# SCH.net
KiCad netlist of a schematic drawn in Altium Designer
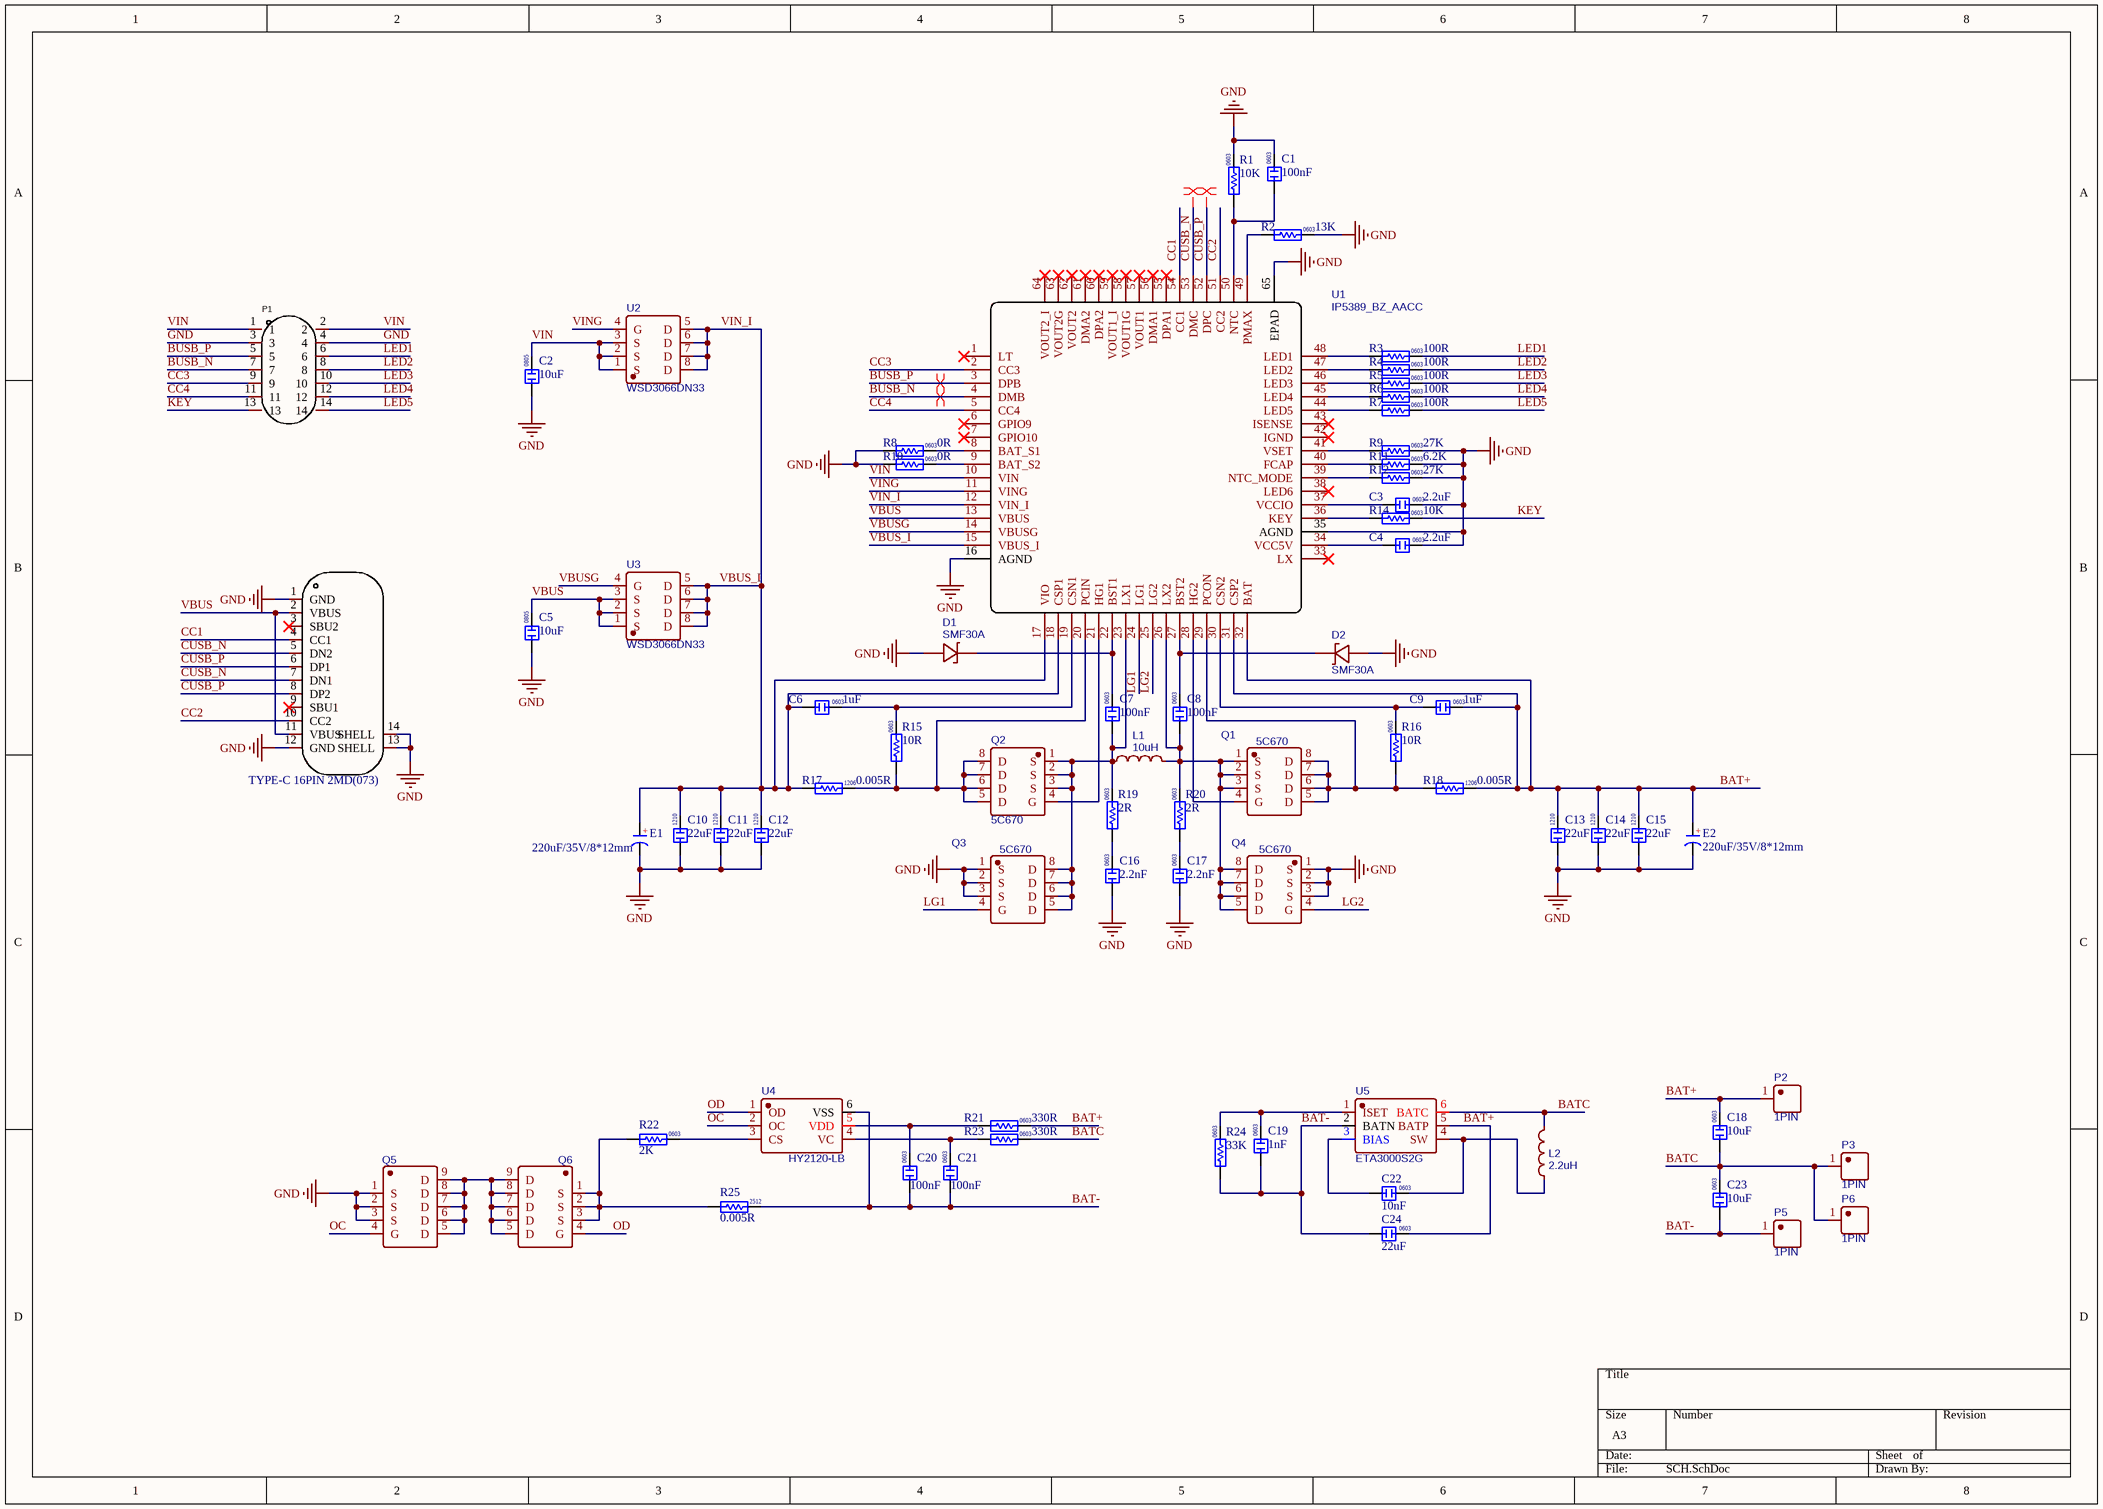
[diagram p0: SCH.SchDoc]

(export (version "E")
  (design (tool "Eeschema 10.0.6"))
  (components
    (comp (ref "C1")
      (value "100nF")
      (footprint "C_0603")
      (description "贴片电容")
      (libsource (lib "VT_SCH_RCL_01") (part "C_0603"))
    )
    (comp (ref "C2")
      (value "10uF")
      (footprint "C_0805")
      (description "贴片电容")
      (libsource (lib "VT_SCH_RCL_01") (part "C_0805"))
    )
    (comp (ref "C3")
      (value "2.2uF")
      (footprint "C_0603")
      (description "贴片电容")
      (libsource (lib "") (part "C_0603_1"))
    )
    (comp (ref "C4")
      (value "2.2uF")
      (footprint "C_0603")
      (description "贴片电容")
      (libsource (lib "") (part "C_0603_1"))
    )
    (comp (ref "C5")
      (value "10uF")
      (footprint "C_0805")
      (description "贴片电容")
      (libsource (lib "VT_SCH_RCL_01") (part "C_0805"))
    )
    (comp (ref "C6")
      (value "1uF")
      (footprint "C_0603")
      (description "贴片电容")
      (libsource (lib "") (part "C_0603_1"))
    )
    (comp (ref "C7")
      (value "100nF")
      (footprint "C_0603")
      (description "贴片电容")
      (libsource (lib "VT_SCH_RCL_01") (part "C_0603"))
    )
    (comp (ref "C8")
      (value "100nF")
      (footprint "C_0603")
      (description "贴片电容")
      (libsource (lib "VT_SCH_RCL_01") (part "C_0603"))
    )
    (comp (ref "C9")
      (value "1uF")
      (footprint "C_0603")
      (description "贴片电容")
      (libsource (lib "") (part "C_0603_1"))
    )
    (comp (ref "C10")
      (value "22uF")
      (footprint "C_1210")
      (description "贴片电容")
      (libsource (lib "VT_SCH_RCL_01") (part "C_1210"))
    )
    (comp (ref "C11")
      (value "22uF")
      (footprint "C_1210")
      (description "贴片电容")
      (libsource (lib "VT_SCH_RCL_01") (part "C_1210"))
    )
    (comp (ref "C12")
      (value "22uF")
      (footprint "C_1210")
      (description "贴片电容")
      (libsource (lib "VT_SCH_RCL_01") (part "C_1210"))
    )
    (comp (ref "C13")
      (value "22uF")
      (footprint "C_1210")
      (description "贴片电容")
      (libsource (lib "VT_SCH_RCL_01") (part "C_1210"))
    )
    (comp (ref "C14")
      (value "22uF")
      (footprint "C_1210")
      (description "贴片电容")
      (libsource (lib "VT_SCH_RCL_01") (part "C_1210"))
    )
    (comp (ref "C15")
      (value "22uF")
      (footprint "C_1210")
      (description "贴片电容")
      (libsource (lib "VT_SCH_RCL_01") (part "C_1210"))
    )
    (comp (ref "C16")
      (value "2.2nF")
      (footprint "C_0603")
      (description "贴片电容")
      (libsource (lib "VT_SCH_RCL_01") (part "C_0603"))
    )
    (comp (ref "C17")
      (value "2.2nF")
      (footprint "C_0603")
      (description "贴片电容")
      (libsource (lib "VT_SCH_RCL_01") (part "C_0603"))
    )
    (comp (ref "C18")
      (value "10uF")
      (footprint "C_0603")
      (description "贴片电容")
      (libsource (lib "VT_SCH_RCL_01") (part "C_0603"))
    )
    (comp (ref "C19")
      (value "1nF")
      (footprint "C_0603")
      (description "贴片电容")
      (libsource (lib "VT_SCH_RCL_01") (part "C_0603"))
    )
    (comp (ref "C20")
      (value "100nF")
      (footprint "C_0603")
      (description "贴片电容")
      (libsource (lib "VT_SCH_RCL_01") (part "C_0603"))
    )
    (comp (ref "C21")
      (value "100nF")
      (footprint "C_0603")
      (description "贴片电容")
      (libsource (lib "VT_SCH_RCL_01") (part "C_0603"))
    )
    (comp (ref "C22")
      (value "10nF")
      (footprint "C_0603")
      (description "贴片电容")
      (libsource (lib "") (part "C_0603_1"))
    )
    (comp (ref "C23")
      (value "10uF")
      (footprint "C_0603")
      (description "贴片电容")
      (libsource (lib "VT_SCH_RCL_01") (part "C_0603"))
    )
    (comp (ref "C24")
      (value "22uF")
      (footprint "C_0603")
      (description "贴片电容")
      (libsource (lib "") (part "C_0603_1"))
    )
    (comp (ref "D1")
      (value "SMF30A")
      (footprint "SOD-123FL_L2.6-W1.6-LS3.4-R-FD")
      (fields (field (name "MANUFACTURER") "(MDD) Jiangsu Yutai Elec") (field (name "CONTRIBUTOR") "LCSC"))
      (libsource (lib "altium-import") (part "root_2_SMF30A_C364281_"))
    )
    (comp (ref "D2")
      (value "SMF30A")
      (footprint "SOD-123FL_L2.6-W1.6-LS3.4-R-FD")
      (fields (field (name "MANUFACTURER") "(MDD) Jiangsu Yutai Elec") (field (name "CONTRIBUTOR") "LCSC"))
      (libsource (lib "altium-import") (part "root_0_SMF30A_C364281_"))
    )
    (comp (ref "E1")
      (value "220uF/35V/8*12mm")
      (footprint "CAP 3.5*8*12_L")
      (description "直插固态电容")
      (fields (field (name "版权归属") "源创客"))
      (libsource (lib "电阻-电容-电感") (part "C-CS"))
    )
    (comp (ref "E2")
      (value "220uF/35V/8*12mm")
      (footprint "CAP 3.5*8*12_L")
      (description "直插固态电容")
      (fields (field (name "版权归属") "源创客"))
      (libsource (lib "电阻-电容-电感") (part "C-CS"))
    )
    (comp (ref "L1")
      (value "10uH")
      (footprint "IND-SMD_L11.0-W10.2")
      (description "PSPMAA1040H-100M-ANP")
      (fields
        (field (name "MANUFACTURER") "Sunlord")
        (field (name "MANUFACTURER PART") "MWSA1206S-5R6MT")
        (field (name "CONTRIBUTOR") "LCSC")
      )
      (libsource (lib "altium-import") (part "root_0_5.6uH_"))
    )
    (comp (ref "L2")
      (value "2.2uH")
      (footprint "L_4*4")
      (fields
        (field (name "MANUFACTURER") "EMTEK")
        (field (name "MANUFACTURER PART") "PHC0420-2R2M-T")
        (field (name "CONTRIBUTOR") "LCSC")
      )
      (libsource (lib "altium-import") (part "root_1_2.2uH_"))
    )
    (comp (ref "P1")
      (value "X1321WR-2x07J-C40D18")
      (footprint "HDR-TH_14P-P1.27-H-M-R2-C7-S1.27-W7.5-N2")
      (description "插针")
      (fields (field (name "MANUFACTURER") "XKB Connectivity(中国星坤)"))
      (libsource (lib "altium-import") (part "root_0_X1321WR-2x07J-C40D18_"))
    )
    (comp (ref "P2")
      (value "1PIN")
      (footprint "1PIN")
      (description "焊点")
      (fields
        (field (name "MANUFACTURER") "ZHENGLING")
        (field (name "MANUFACTURER PART") "Z-211-0311-0021-001")
        (field (name "CONTRIBUTOR") "LCSC")
      )
      (libsource (lib "DHO800_Battery_Pack_IP5389_V1.0_2") (part "1PIN"))
    )
    (comp (ref "P3")
      (value "1PIN")
      (footprint "1PIN")
      (description "焊点")
      (fields
        (field (name "MANUFACTURER") "ZHENGLING")
        (field (name "MANUFACTURER PART") "Z-211-0311-0021-001")
        (field (name "CONTRIBUTOR") "LCSC")
      )
      (libsource (lib "DHO800_Battery_Pack_IP5389_V1.0_2") (part "1PIN"))
    )
    (comp (ref "P5")
      (value "1PIN")
      (footprint "1PIN")
      (description "焊点")
      (fields
        (field (name "MANUFACTURER") "ZHENGLING")
        (field (name "MANUFACTURER PART") "Z-211-0311-0021-001")
        (field (name "CONTRIBUTOR") "LCSC")
      )
      (libsource (lib "DHO800_Battery_Pack_IP5389_V1.0_2") (part "1PIN"))
    )
    (comp (ref "P6")
      (value "1PIN")
      (footprint "1PIN")
      (description "焊点")
      (fields
        (field (name "MANUFACTURER") "ZHENGLING")
        (field (name "MANUFACTURER PART") "Z-211-0311-0021-001")
        (field (name "CONTRIBUTOR") "LCSC")
      )
      (libsource (lib "DHO800_Battery_Pack_IP5389_V1.0_2") (part "1PIN"))
    )
    (comp (ref "Q1")
      (value "5C670")
      (footprint "DFN-5_L6.1-W5.1-P1.27-BL")
      (description "NTMFS5C670NLT1G")
      (fields (field (name "MANUFACTURER") "ON Semicon") (field (name "CONTRIBUTOR") "LCSC"))
      (libsource (lib "") (part "root_0_5C670__1"))
    )
    (comp (ref "Q2")
      (value "5C670")
      (footprint "DFN-5_L6.1-W5.1-P1.27-BL")
      (description "NTMFS5C670NLT1G")
      (fields (field (name "MANUFACTURER") "ON Semicon") (field (name "CONTRIBUTOR") "LCSC"))
      (libsource (lib "altium-import") (part "root_0_5C670_"))
    )
    (comp (ref "Q3")
      (value "5C670")
      (footprint "DFN-5_L6.1-W5.1-P1.27-BL")
      (description "NTMFS5C670NLT1G")
      (fields (field (name "MANUFACTURER") "ON Semicon") (field (name "CONTRIBUTOR") "LCSC"))
      (libsource (lib "") (part "root_0_5C670__1"))
    )
    (comp (ref "Q4")
      (value "5C670")
      (footprint "DFN-5_L6.1-W5.1-P1.27-BL")
      (description "NTMFS5C670NLT1G")
      (fields (field (name "MANUFACTURER") "ON Semicon") (field (name "CONTRIBUTOR") "LCSC"))
      (libsource (lib "altium-import") (part "root_0_5C670_"))
    )
    (comp (ref "Q5")
      (value "TPH1R403NL")
      (footprint "DSOP-8_L5.0-W5.0-P1.27-LS6.0-BL-EP")
      (fields
        (field (name "MANUFACTURER") "Vishay Intertech")
        (field (name "MANUFACTURER PART") "SIRA12DP-T1-GE3")
        (field (name "CONTRIBUTOR") "LCSC")
      )
      (libsource (lib "") (part "root_0_SIRA12DP-T1-GE3__1"))
    )
    (comp (ref "Q6")
      (value "TPH1R403NL")
      (footprint "DSOP-8_L5.0-W5.0-P1.27-LS6.0-BL-EP")
      (fields
        (field (name "MANUFACTURER") "Vishay Intertech")
        (field (name "MANUFACTURER PART") "SIRA12DP-T1-GE3")
        (field (name "CONTRIBUTOR") "LCSC")
      )
      (libsource (lib "altium-import") (part "root_0_SIRA12DP-T1-GE3_"))
    )
    (comp (ref "R1")
      (value "10K")
      (footprint "R_0603")
      (description "贴片电阻")
      (libsource (lib "") (part "R_0603_1"))
    )
    (comp (ref "R2")
      (value "13K")
      (footprint "R_0603")
      (description "贴片电阻")
      (libsource (lib "VT_SCH_RCL_01") (part "R_0603"))
    )
    (comp (ref "R3")
      (value "100R")
      (footprint "R_0603")
      (description "贴片电阻")
      (libsource (lib "VT_SCH_RCL_01") (part "R_0603"))
    )
    (comp (ref "R4")
      (value "100R")
      (footprint "R_0603")
      (description "贴片电阻")
      (libsource (lib "VT_SCH_RCL_01") (part "R_0603"))
    )
    (comp (ref "R5")
      (value "100R")
      (footprint "R_0603")
      (description "贴片电阻")
      (libsource (lib "VT_SCH_RCL_01") (part "R_0603"))
    )
    (comp (ref "R6")
      (value "100R")
      (footprint "R_0603")
      (description "贴片电阻")
      (libsource (lib "VT_SCH_RCL_01") (part "R_0603"))
    )
    (comp (ref "R7")
      (value "100R")
      (footprint "R_0603")
      (description "贴片电阻")
      (libsource (lib "VT_SCH_RCL_01") (part "R_0603"))
    )
    (comp (ref "R8")
      (value "0R")
      (footprint "R_0603")
      (description "贴片电阻")
      (libsource (lib "VT_SCH_RCL_01") (part "R_0603"))
    )
    (comp (ref "R9")
      (value "27K")
      (footprint "R_0603")
      (description "贴片电阻")
      (libsource (lib "VT_SCH_RCL_01") (part "R_0603"))
    )
    (comp (ref "R10")
      (value "0R")
      (footprint "R_0603")
      (description "贴片电阻")
      (libsource (lib "VT_SCH_RCL_01") (part "R_0603"))
    )
    (comp (ref "R11")
      (value "6.2K")
      (footprint "R_0603")
      (description "贴片电阻")
      (libsource (lib "VT_SCH_RCL_01") (part "R_0603"))
    )
    (comp (ref "R12")
      (value "27K")
      (footprint "R_0603")
      (description "贴片电阻")
      (libsource (lib "VT_SCH_RCL_01") (part "R_0603"))
    )
    (comp (ref "R14")
      (value "10K")
      (footprint "R_0603")
      (description "贴片电阻")
      (libsource (lib "VT_SCH_RCL_01") (part "R_0603"))
    )
    (comp (ref "R15")
      (value "10R")
      (footprint "R_0603")
      (description "贴片电阻")
      (libsource (lib "") (part "R_0603_1"))
    )
    (comp (ref "R16")
      (value "10R")
      (footprint "R_0603")
      (description "贴片电阻")
      (libsource (lib "") (part "R_0603_1"))
    )
    (comp (ref "R17")
      (value "0.005R")
      (footprint "R_1206")
      (description "贴片电阻")
      (libsource (lib "VT_SCH_RCL_01") (part "R_1206"))
    )
    (comp (ref "R18")
      (value "0.005R")
      (footprint "R_1206")
      (description "贴片电阻")
      (libsource (lib "VT_SCH_RCL_01") (part "R_1206"))
    )
    (comp (ref "R19")
      (value "2R")
      (footprint "R_0603")
      (description "贴片电阻")
      (libsource (lib "") (part "R_0603_1"))
    )
    (comp (ref "R20")
      (value "2R")
      (footprint "R_0603")
      (description "贴片电阻")
      (libsource (lib "") (part "R_0603_1"))
    )
    (comp (ref "R21")
      (value "330R")
      (footprint "R_0603")
      (description "贴片电阻")
      (libsource (lib "VT_SCH_RCL_01") (part "R_0603"))
    )
    (comp (ref "R22")
      (value "2K")
      (footprint "R_0603")
      (description "贴片电阻")
      (libsource (lib "VT_SCH_RCL_01") (part "R_0603"))
    )
    (comp (ref "R23")
      (value "330R")
      (footprint "R_0603")
      (description "贴片电阻")
      (libsource (lib "VT_SCH_RCL_01") (part "R_0603"))
    )
    (comp (ref "R24")
      (value "33K")
      (footprint "R_0603")
      (description "贴片电阻")
      (libsource (lib "") (part "R_0603_1"))
    )
    (comp (ref "R25")
      (value "0.005R")
      (footprint "R_2512")
      (description "贴片电阻")
      (libsource (lib "VT_SCH_RCL_01") (part "R_2512"))
    )
    (comp (ref "U1")
      (value "IP5389_BZ_AACC")
      (footprint "QFN-64_IP5389")
      (description "芯片")
      (fields (field (name "CONTRIBUTOR") "LoveLoli"))
      (libsource (lib "DHO800_Battery_Pack_IP5389_V1.0_2") (part "IP5389_BZ_AACC"))
    )
    (comp (ref "U2")
      (value "WSD3066DN33")
      (footprint "DFN-8_L3.3-W3.3-P0.65-BL")
      (description "NMOS管")
      (fields
        (field (name "MANUFACTURER PART") "NTMFS5C670NLT1G")
        (field (name "MANUFACTURER") "ON Semicon")
        (field (name "CONTRIBUTOR") "LCSC")
      )
      (libsource (lib "DHO800_Battery_Pack_IP5389_V1.0_2") (part "WSD3066DN33"))
    )
    (comp (ref "U3")
      (value "WSD3066DN33")
      (footprint "DFN-8_L3.3-W3.3-P0.65-BL")
      (description "NMOS管")
      (fields
        (field (name "MANUFACTURER PART") "NTMFS5C670NLT1G")
        (field (name "MANUFACTURER") "ON Semicon")
        (field (name "CONTRIBUTOR") "LCSC")
      )
      (libsource (lib "DHO800_Battery_Pack_IP5389_V1.0_2") (part "WSD3066DN33"))
    )
    (comp (ref "U4")
      (value "HY2120-LB")
      (footprint "SOT-23-6_L2.9-W1.6-P0.95-LS2.8-BR")
      (fields (field (name "MANUFACTURER") "HYCON") (field (name "CONTRIBUTOR") "LCSC"))
      (libsource (lib "altium-import") (part "root_0_HY2120-LB_"))
    )
    (comp (ref "U5")
      (value "ETA3000S2G")
      (footprint "SOT-23-6_L2.9-W1.6-P0.95-LS2.8-BL")
      (description "芯片")
      (fields (field (name "MANUFACTURER") "ETA(钰泰)") (field (name "CONTRIBUTOR") "ryq1212"))
      (libsource (lib "altium-import") (part "root_0_ETA3000S2G_"))
    )
    (comp (ref "USB1")
      (value "TYPE-C 16PIN 2MD(073)")
      (footprint "USB-C-SMD_TYPE-C-6PIN-2MD-073")
      (description "USB C母座")
      (fields (field (name "MANUFACTURER") "SHOU HAN(首韩)"))
      (libsource (lib "DHO800_Battery_Pack_IP5389_V1.0") (part "TYPE-C 16PIN 2MD(073)"))
    )
  )
  (nets
    (net (code "1") (name "/BAT+") (class "Default")
      (node (ref "C13") (pin "2") (pinfunction "2_2") (pintype "passive"))
      (node (ref "C14") (pin "2") (pinfunction "2_2") (pintype "passive"))
      (node (ref "C15") (pin "2") (pinfunction "2_2") (pintype "passive"))
      (node (ref "C18") (pin "2") (pinfunction "2_2") (pintype "passive"))
      (node (ref "C24") (pin "2") (pinfunction "2_2") (pintype "passive"))
      (node (ref "C9") (pin "2") (pinfunction "2_2") (pintype "passive"))
      (node (ref "E2") (pin "1") (pinfunction "A_1") (pintype "passive"))
      (node (ref "P2") (pin "1") (pintype "passive"))
      (node (ref "R18") (pin "2") (pinfunction "2_2") (pintype "passive"))
      (node (ref "R21") (pin "2") (pinfunction "2_2") (pintype "passive"))
      (node (ref "U1") (pin "31") (pinfunction "CSP2_31") (pintype "passive"))
      (node (ref "U1") (pin "32") (pinfunction "BAT_32") (pintype "passive"))
      (node (ref "U5") (pin "5") (pinfunction "BATP_5") (pintype "passive"))
    )
    (net (code "2") (name "/BAT-") (class "Default")
      (node (ref "C19") (pin "1") (pinfunction "1_1") (pintype "passive"))
      (node (ref "C20") (pin "1") (pinfunction "1_1") (pintype "passive"))
      (node (ref "C21") (pin "1") (pinfunction "1_1") (pintype "passive"))
      (node (ref "C23") (pin "1") (pinfunction "1_1") (pintype "passive"))
      (node (ref "C24") (pin "1") (pinfunction "1_1") (pintype "passive"))
      (node (ref "P5") (pin "1") (pintype "passive"))
      (node (ref "R24") (pin "1") (pinfunction "1_1") (pintype "passive"))
      (node (ref "R25") (pin "2") (pinfunction "2_2") (pintype "passive"))
      (node (ref "U4") (pin "6") (pinfunction "VSS_6") (pintype "passive"))
      (node (ref "U5") (pin "2") (pinfunction "BATN_2") (pintype "passive"))
    )
    (net (code "3") (name "/BATC") (class "Default")
      (node (ref "C18") (pin "1") (pinfunction "1_1") (pintype "passive"))
      (node (ref "C23") (pin "2") (pinfunction "2_2") (pintype "passive"))
      (node (ref "L2") (pin "2") (pinfunction "2_2") (pintype "passive"))
      (node (ref "P3") (pin "1") (pintype "passive"))
      (node (ref "P6") (pin "1") (pintype "passive"))
      (node (ref "R23") (pin "2") (pinfunction "2_2") (pintype "passive"))
      (node (ref "U5") (pin "6") (pinfunction "BATC_6") (pintype "passive"))
    )
    (net (code "4") (name "/BUSB_N") (class "Default")
      (node (ref "P1") (pin "7") (pinfunction "7_7") (pintype "passive"))
      (node (ref "U1") (pin "4") (pinfunction "DMB_4") (pintype "passive"))
    )
    (net (code "5") (name "/BUSB_P") (class "Default")
      (node (ref "P1") (pin "5") (pinfunction "5_5") (pintype "passive"))
      (node (ref "U1") (pin "3") (pinfunction "DPB_3") (pintype "passive"))
    )
    (net (code "6") (name "/CC1") (class "Default")
      (node (ref "U1") (pin "54") (pinfunction "CC1_54") (pintype "passive"))
      (node (ref "USB1") (pin "4") (pinfunction "CC1_4") (pintype "passive"))
    )
    (net (code "7") (name "/CC2") (class "Default")
      (node (ref "U1") (pin "51") (pinfunction "CC2_51") (pintype "passive"))
      (node (ref "USB1") (pin "10") (pinfunction "CC2_10") (pintype "passive"))
    )
    (net (code "8") (name "/CC3") (class "Default")
      (node (ref "P1") (pin "9") (pinfunction "9_9") (pintype "passive"))
      (node (ref "U1") (pin "2") (pinfunction "CC3_2") (pintype "passive"))
    )
    (net (code "9") (name "/CC4") (class "Default")
      (node (ref "P1") (pin "11") (pinfunction "11_11") (pintype "passive"))
      (node (ref "U1") (pin "5") (pinfunction "CC4_5") (pintype "passive"))
    )
    (net (code "10") (name "/CUSB_N") (class "Default")
      (node (ref "U1") (pin "53") (pinfunction "DMC_53") (pintype "passive"))
      (node (ref "USB1") (pin "5") (pinfunction "DN2_5") (pintype "passive"))
      (node (ref "USB1") (pin "7") (pinfunction "DN1_7") (pintype "passive"))
    )
    (net (code "11") (name "/CUSB_P") (class "Default")
      (node (ref "U1") (pin "52") (pinfunction "DPC_52") (pintype "passive"))
      (node (ref "USB1") (pin "6") (pinfunction "DP1_6") (pintype "passive"))
      (node (ref "USB1") (pin "8") (pinfunction "DP2_8") (pintype "passive"))
    )
    (net (code "12") (name "/KEY") (class "Default")
      (node (ref "P1") (pin "13") (pinfunction "13_13") (pintype "passive"))
      (node (ref "R14") (pin "2") (pinfunction "2_2") (pintype "passive"))
    )
    (net (code "13") (name "/LED1") (class "Default")
      (node (ref "P1") (pin "6") (pinfunction "6_6") (pintype "passive"))
      (node (ref "R3") (pin "2") (pinfunction "2_2") (pintype "passive"))
    )
    (net (code "14") (name "/LED2") (class "Default")
      (node (ref "P1") (pin "8") (pinfunction "8_8") (pintype "passive"))
      (node (ref "R4") (pin "2") (pinfunction "2_2") (pintype "passive"))
    )
    (net (code "15") (name "/LED3") (class "Default")
      (node (ref "P1") (pin "10") (pinfunction "10_10") (pintype "passive"))
      (node (ref "R5") (pin "2") (pinfunction "2_2") (pintype "passive"))
    )
    (net (code "16") (name "/LED4") (class "Default")
      (node (ref "P1") (pin "12") (pinfunction "12_12") (pintype "passive"))
      (node (ref "R6") (pin "2") (pinfunction "2_2") (pintype "passive"))
    )
    (net (code "17") (name "/LED5") (class "Default")
      (node (ref "P1") (pin "14") (pinfunction "14_14") (pintype "passive"))
      (node (ref "R7") (pin "2") (pinfunction "2_2") (pintype "passive"))
    )
    (net (code "18") (name "/LG1") (class "Default")
      (node (ref "Q3") (pin "4") (pinfunction "G_4") (pintype "passive"))
      (node (ref "U1") (pin "24") (pinfunction "LG1_24") (pintype "passive"))
    )
    (net (code "19") (name "/LG2") (class "Default")
      (node (ref "Q4") (pin "4") (pinfunction "G_4") (pintype "passive"))
      (node (ref "U1") (pin "25") (pinfunction "LG2_25") (pintype "passive"))
    )
    (net (code "20") (name "/OC") (class "Default")
      (node (ref "Q5") (pin "4") (pinfunction "G_4") (pintype "passive"))
      (node (ref "U4") (pin "2") (pinfunction "OC_2") (pintype "passive"))
    )
    (net (code "21") (name "/OD") (class "Default")
      (node (ref "Q6") (pin "4") (pinfunction "G_4") (pintype "passive"))
      (node (ref "U4") (pin "1") (pinfunction "OD_1") (pintype "passive"))
    )
    (net (code "22") (name "/VBUS") (class "Default")
      (node (ref "C5") (pin "2") (pinfunction "2_2") (pintype "passive"))
      (node (ref "U1") (pin "13") (pinfunction "VBUS_13") (pintype "passive"))
      (node (ref "U3") (pin "1") (pinfunction "S_1") (pintype "passive"))
      (node (ref "U3") (pin "2") (pinfunction "S_2") (pintype "passive"))
      (node (ref "U3") (pin "3") (pinfunction "S_3") (pintype "passive"))
      (node (ref "USB1") (pin "11") (pinfunction "VBUS_11") (pintype "passive"))
      (node (ref "USB1") (pin "2") (pinfunction "VBUS_2") (pintype "passive"))
    )
    (net (code "23") (name "/VBUSG") (class "Default")
      (node (ref "U1") (pin "14") (pinfunction "VBUSG_14") (pintype "passive"))
      (node (ref "U3") (pin "4") (pinfunction "G_4") (pintype "passive"))
    )
    (net (code "24") (name "/VBUS_I") (class "Default")
      (node (ref "C10") (pin "2") (pinfunction "2_2") (pintype "passive"))
      (node (ref "C11") (pin "2") (pinfunction "2_2") (pintype "passive"))
      (node (ref "C12") (pin "2") (pinfunction "2_2") (pintype "passive"))
      (node (ref "C6") (pin "1") (pinfunction "1_1") (pintype "passive"))
      (node (ref "E1") (pin "1") (pinfunction "A_1") (pintype "passive"))
      (node (ref "R17") (pin "1") (pinfunction "1_1") (pintype "passive"))
      (node (ref "U1") (pin "12") (pinfunction "VIN_I_12") (pintype "passive"))
      (node (ref "U1") (pin "15") (pinfunction "VBUS_I_15") (pintype "passive"))
      (node (ref "U1") (pin "17") (pinfunction "VIO_17") (pintype "passive"))
      (node (ref "U1") (pin "18") (pinfunction "CSP1_18") (pintype "passive"))
      (node (ref "U2") (pin "5") (pinfunction "D_5") (pintype "passive"))
      (node (ref "U2") (pin "6") (pinfunction "D_6") (pintype "passive"))
      (node (ref "U2") (pin "7") (pinfunction "D_7") (pintype "passive"))
      (node (ref "U2") (pin "8") (pinfunction "D_8") (pintype "passive"))
      (node (ref "U3") (pin "5") (pinfunction "D_5") (pintype "passive"))
      (node (ref "U3") (pin "6") (pinfunction "D_6") (pintype "passive"))
      (node (ref "U3") (pin "7") (pinfunction "D_7") (pintype "passive"))
      (node (ref "U3") (pin "8") (pinfunction "D_8") (pintype "passive"))
    )
    (net (code "25") (name "/VIN") (class "Default")
      (node (ref "C2") (pin "2") (pinfunction "2_2") (pintype "passive"))
      (node (ref "P1") (pin "1") (pinfunction "1_1") (pintype "passive"))
      (node (ref "P1") (pin "2") (pinfunction "2_2") (pintype "passive"))
      (node (ref "U1") (pin "10") (pinfunction "VIN_10") (pintype "passive"))
      (node (ref "U2") (pin "1") (pinfunction "S_1") (pintype "passive"))
      (node (ref "U2") (pin "2") (pinfunction "S_2") (pintype "passive"))
      (node (ref "U2") (pin "3") (pinfunction "S_3") (pintype "passive"))
    )
    (net (code "26") (name "/VING") (class "Default")
      (node (ref "U1") (pin "11") (pinfunction "VING_11") (pintype "passive"))
      (node (ref "U2") (pin "4") (pinfunction "G_4") (pintype "passive"))
    )
    (net (code "27") (name "GND") (class "Default")
      (node (ref "C1") (pin "2") (pinfunction "2_2") (pintype "passive"))
      (node (ref "C10") (pin "1") (pinfunction "1_1") (pintype "passive"))
      (node (ref "C11") (pin "1") (pinfunction "1_1") (pintype "passive"))
      (node (ref "C12") (pin "1") (pinfunction "1_1") (pintype "passive"))
      (node (ref "C13") (pin "1") (pinfunction "1_1") (pintype "passive"))
      (node (ref "C14") (pin "1") (pinfunction "1_1") (pintype "passive"))
      (node (ref "C15") (pin "1") (pinfunction "1_1") (pintype "passive"))
      (node (ref "C16") (pin "1") (pinfunction "1_1") (pintype "passive"))
      (node (ref "C17") (pin "1") (pinfunction "1_1") (pintype "passive"))
      (node (ref "C2") (pin "1") (pinfunction "1_1") (pintype "passive"))
      (node (ref "C3") (pin "2") (pinfunction "2_2") (pintype "passive"))
      (node (ref "C4") (pin "2") (pinfunction "2_2") (pintype "passive"))
      (node (ref "C5") (pin "1") (pinfunction "1_1") (pintype "passive"))
      (node (ref "D1") (pin "2") (pinfunction "A_2") (pintype "passive"))
      (node (ref "D2") (pin "2") (pinfunction "A_2") (pintype "passive"))
      (node (ref "E1") (pin "2") (pinfunction "K_2") (pintype "passive"))
      (node (ref "E2") (pin "2") (pinfunction "K_2") (pintype "passive"))
      (node (ref "P1") (pin "3") (pinfunction "3_3") (pintype "passive"))
      (node (ref "P1") (pin "4") (pinfunction "4_4") (pintype "passive"))
      (node (ref "Q3") (pin "1") (pinfunction "S_1") (pintype "passive"))
      (node (ref "Q3") (pin "2") (pinfunction "S_2") (pintype "passive"))
      (node (ref "Q3") (pin "3") (pinfunction "S_3") (pintype "passive"))
      (node (ref "Q4") (pin "1") (pinfunction "S_1") (pintype "passive"))
      (node (ref "Q4") (pin "2") (pinfunction "S_2") (pintype "passive"))
      (node (ref "Q4") (pin "3") (pinfunction "S_3") (pintype "passive"))
      (node (ref "Q5") (pin "1") (pinfunction "S_1") (pintype "passive"))
      (node (ref "Q5") (pin "2") (pinfunction "S_2") (pintype "passive"))
      (node (ref "Q5") (pin "3") (pinfunction "S_3") (pintype "passive"))
      (node (ref "R1") (pin "2") (pinfunction "2_2") (pintype "passive"))
      (node (ref "R10") (pin "1") (pinfunction "1_1") (pintype "passive"))
      (node (ref "R11") (pin "2") (pinfunction "2_2") (pintype "passive"))
      (node (ref "R12") (pin "2") (pinfunction "2_2") (pintype "passive"))
      (node (ref "R2") (pin "2") (pinfunction "2_2") (pintype "passive"))
      (node (ref "R8") (pin "1") (pinfunction "1_1") (pintype "passive"))
      (node (ref "R9") (pin "2") (pinfunction "2_2") (pintype "passive"))
      (node (ref "U1") (pin "16") (pinfunction "AGND_16") (pintype "passive"))
      (node (ref "U1") (pin "35") (pinfunction "AGND_35") (pintype "passive"))
      (node (ref "U1") (pin "65") (pinfunction "EPAD_65") (pintype "passive"))
      (node (ref "USB1") (pin "1") (pinfunction "GND_1") (pintype "passive"))
      (node (ref "USB1") (pin "12") (pinfunction "GND_12") (pintype "passive"))
      (node (ref "USB1") (pin "13") (pinfunction "SHELL_13") (pintype "passive"))
      (node (ref "USB1") (pin "14") (pinfunction "SHELL_14") (pintype "passive"))
    )
    (net (code "28") (name "Net-(C16-Pad2)") (class "Default")
      (node (ref "C16") (pin "2") (pinfunction "2_2") (pintype "passive"))
      (node (ref "R19") (pin "1") (pinfunction "1_1") (pintype "passive"))
    )
    (net (code "29") (name "Net-(C17-Pad2)") (class "Default")
      (node (ref "C17") (pin "2") (pinfunction "2_2") (pintype "passive"))
      (node (ref "R20") (pin "1") (pinfunction "1_1") (pintype "passive"))
    )
    (net (code "30") (name "Net-(D1-K)") (class "Default")
      (node (ref "C7") (pin "2") (pinfunction "2_2") (pintype "passive"))
      (node (ref "D1") (pin "1") (pinfunction "K_1") (pintype "passive"))
      (node (ref "U1") (pin "22") (pinfunction "BST1_22") (pintype "passive"))
    )
    (net (code "31") (name "Net-(D2-K)") (class "Default")
      (node (ref "C8") (pin "2") (pinfunction "2_2") (pintype "passive"))
      (node (ref "D2") (pin "1") (pinfunction "K_1") (pintype "passive"))
      (node (ref "U1") (pin "27") (pinfunction "BST2_27") (pintype "passive"))
    )
    (net (code "32") (name "Net-(Q1-G)") (class "Default")
      (node (ref "Q1") (pin "4") (pinfunction "G_4") (pintype "passive"))
      (node (ref "U1") (pin "28") (pinfunction "HG2_28") (pintype "passive"))
    )
    (net (code "33") (name "Net-(Q2-G)") (class "Default")
      (node (ref "Q2") (pin "4") (pinfunction "G_4") (pintype "passive"))
      (node (ref "U1") (pin "21") (pinfunction "HG1_21") (pintype "passive"))
    )
    (net (code "34") (name "Net-(Q5-D-Pad5)") (class "Default")
      (node (ref "Q5") (pin "5") (pinfunction "D_5") (pintype "passive"))
      (node (ref "Q5") (pin "6") (pinfunction "D_6") (pintype "passive"))
      (node (ref "Q5") (pin "7") (pinfunction "D_7") (pintype "passive"))
      (node (ref "Q5") (pin "8") (pinfunction "D_8") (pintype "passive"))
      (node (ref "Q5") (pin "9") (pinfunction "D_9") (pintype "passive"))
      (node (ref "Q6") (pin "5") (pinfunction "D_5") (pintype "passive"))
      (node (ref "Q6") (pin "6") (pinfunction "D_6") (pintype "passive"))
      (node (ref "Q6") (pin "7") (pinfunction "D_7") (pintype "passive"))
      (node (ref "Q6") (pin "8") (pinfunction "D_8") (pintype "passive"))
      (node (ref "Q6") (pin "9") (pinfunction "D_9") (pintype "passive"))
    )
    (net (code "35") (name "Net-(Q6-S-Pad1)") (class "Default")
      (node (ref "Q6") (pin "1") (pinfunction "S_1") (pintype "passive"))
      (node (ref "Q6") (pin "2") (pinfunction "S_2") (pintype "passive"))
      (node (ref "Q6") (pin "3") (pinfunction "S_3") (pintype "passive"))
      (node (ref "R22") (pin "1") (pinfunction "1_1") (pintype "passive"))
      (node (ref "R25") (pin "1") (pinfunction "1_1") (pintype "passive"))
    )
    (net (code "36") (name "Net-(U1-BAT_S1)") (class "Default")
      (node (ref "R8") (pin "2") (pinfunction "2_2") (pintype "passive"))
      (node (ref "U1") (pin "8") (pinfunction "BAT_S1_8") (pintype "passive"))
    )
    (net (code "37") (name "Net-(U1-BAT_S2)") (class "Default")
      (node (ref "R10") (pin "2") (pinfunction "2_2") (pintype "passive"))
      (node (ref "U1") (pin "9") (pinfunction "BAT_S2_9") (pintype "passive"))
    )
    (net (code "38") (name "Net-(U1-CSN1)") (class "Default")
      (node (ref "C6") (pin "2") (pinfunction "2_2") (pintype "passive"))
      (node (ref "R15") (pin "2") (pinfunction "2_2") (pintype "passive"))
      (node (ref "U1") (pin "19") (pinfunction "CSN1_19") (pintype "passive"))
    )
    (net (code "39") (name "Net-(U1-CSN2)") (class "Default")
      (node (ref "C9") (pin "1") (pinfunction "1_1") (pintype "passive"))
      (node (ref "R16") (pin "2") (pinfunction "2_2") (pintype "passive"))
      (node (ref "U1") (pin "30") (pinfunction "CSN2_30") (pintype "passive"))
    )
    (net (code "40") (name "Net-(U1-FCAP)") (class "Default")
      (node (ref "R11") (pin "1") (pinfunction "1_1") (pintype "passive"))
      (node (ref "U1") (pin "40") (pinfunction "FCAP_40") (pintype "passive"))
    )
    (net (code "41") (name "Net-(U1-KEY)") (class "Default")
      (node (ref "R14") (pin "1") (pinfunction "1_1") (pintype "passive"))
      (node (ref "U1") (pin "36") (pinfunction "KEY_36") (pintype "passive"))
    )
    (net (code "42") (name "Net-(U1-LED1)") (class "Default")
      (node (ref "R3") (pin "1") (pinfunction "1_1") (pintype "passive"))
      (node (ref "U1") (pin "48") (pinfunction "LED1_48") (pintype "passive"))
    )
    (net (code "43") (name "Net-(U1-LED2)") (class "Default")
      (node (ref "R4") (pin "1") (pinfunction "1_1") (pintype "passive"))
      (node (ref "U1") (pin "47") (pinfunction "LED2_47") (pintype "passive"))
    )
    (net (code "44") (name "Net-(U1-LED3)") (class "Default")
      (node (ref "R5") (pin "1") (pinfunction "1_1") (pintype "passive"))
      (node (ref "U1") (pin "46") (pinfunction "LED3_46") (pintype "passive"))
    )
    (net (code "45") (name "Net-(U1-LED4)") (class "Default")
      (node (ref "R6") (pin "1") (pinfunction "1_1") (pintype "passive"))
      (node (ref "U1") (pin "45") (pinfunction "LED4_45") (pintype "passive"))
    )
    (net (code "46") (name "Net-(U1-LED5)") (class "Default")
      (node (ref "R7") (pin "1") (pinfunction "1_1") (pintype "passive"))
      (node (ref "U1") (pin "44") (pinfunction "LED5_44") (pintype "passive"))
    )
    (net (code "47") (name "Net-(U1-LX1)") (class "Default")
      (node (ref "C7") (pin "1") (pinfunction "1_1") (pintype "passive"))
      (node (ref "L1") (pin "1") (pinfunction "1_1") (pintype "passive"))
      (node (ref "Q2") (pin "1") (pinfunction "S_1") (pintype "passive"))
      (node (ref "Q2") (pin "2") (pinfunction "S_2") (pintype "passive"))
      (node (ref "Q2") (pin "3") (pinfunction "S_3") (pintype "passive"))
      (node (ref "Q3") (pin "5") (pinfunction "D_5") (pintype "passive"))
      (node (ref "Q3") (pin "6") (pinfunction "D_6") (pintype "passive"))
      (node (ref "Q3") (pin "7") (pinfunction "D_7") (pintype "passive"))
      (node (ref "Q3") (pin "8") (pinfunction "D_8") (pintype "passive"))
      (node (ref "R19") (pin "2") (pinfunction "2_2") (pintype "passive"))
      (node (ref "U1") (pin "23") (pinfunction "LX1_23") (pintype "passive"))
    )
    (net (code "48") (name "Net-(U1-LX2)") (class "Default")
      (node (ref "C8") (pin "1") (pinfunction "1_1") (pintype "passive"))
      (node (ref "L1") (pin "2") (pinfunction "2_2") (pintype "passive"))
      (node (ref "Q1") (pin "1") (pinfunction "S_1") (pintype "passive"))
      (node (ref "Q1") (pin "2") (pinfunction "S_2") (pintype "passive"))
      (node (ref "Q1") (pin "3") (pinfunction "S_3") (pintype "passive"))
      (node (ref "Q4") (pin "5") (pinfunction "D_5") (pintype "passive"))
      (node (ref "Q4") (pin "6") (pinfunction "D_6") (pintype "passive"))
      (node (ref "Q4") (pin "7") (pinfunction "D_7") (pintype "passive"))
      (node (ref "Q4") (pin "8") (pinfunction "D_8") (pintype "passive"))
      (node (ref "R20") (pin "2") (pinfunction "2_2") (pintype "passive"))
      (node (ref "U1") (pin "26") (pinfunction "LX2_26") (pintype "passive"))
    )
    (net (code "49") (name "Net-(U1-NTC)") (class "Default")
      (node (ref "C1") (pin "1") (pinfunction "1_1") (pintype "passive"))
      (node (ref "R1") (pin "1") (pinfunction "1_1") (pintype "passive"))
      (node (ref "U1") (pin "50") (pinfunction "NTC_50") (pintype "passive"))
    )
    (net (code "50") (name "Net-(U1-NTC_MODE)") (class "Default")
      (node (ref "R12") (pin "1") (pinfunction "1_1") (pintype "passive"))
      (node (ref "U1") (pin "39") (pinfunction "NTC_MODE_39") (pintype "passive"))
    )
    (net (code "51") (name "Net-(U1-PCIN)") (class "Default")
      (node (ref "Q2") (pin "5") (pinfunction "D_5") (pintype "passive"))
      (node (ref "Q2") (pin "6") (pinfunction "D_6") (pintype "passive"))
      (node (ref "Q2") (pin "7") (pinfunction "D_7") (pintype "passive"))
      (node (ref "Q2") (pin "8") (pinfunction "D_8") (pintype "passive"))
      (node (ref "R15") (pin "1") (pinfunction "1_1") (pintype "passive"))
      (node (ref "R17") (pin "2") (pinfunction "2_2") (pintype "passive"))
      (node (ref "U1") (pin "20") (pinfunction "PCIN_20") (pintype "passive"))
    )
    (net (code "52") (name "Net-(U1-PCON)") (class "Default")
      (node (ref "Q1") (pin "5") (pinfunction "D_5") (pintype "passive"))
      (node (ref "Q1") (pin "6") (pinfunction "D_6") (pintype "passive"))
      (node (ref "Q1") (pin "7") (pinfunction "D_7") (pintype "passive"))
      (node (ref "Q1") (pin "8") (pinfunction "D_8") (pintype "passive"))
      (node (ref "R16") (pin "1") (pinfunction "1_1") (pintype "passive"))
      (node (ref "R18") (pin "1") (pinfunction "1_1") (pintype "passive"))
      (node (ref "U1") (pin "29") (pinfunction "PCON_29") (pintype "passive"))
    )
    (net (code "53") (name "Net-(U1-PMAX)") (class "Default")
      (node (ref "R2") (pin "1") (pinfunction "1_1") (pintype "passive"))
      (node (ref "U1") (pin "49") (pinfunction "PMAX_49") (pintype "passive"))
    )
    (net (code "54") (name "Net-(U1-VCC5V)") (class "Default")
      (node (ref "C4") (pin "1") (pinfunction "1_1") (pintype "passive"))
      (node (ref "U1") (pin "34") (pinfunction "VCC5V_34") (pintype "passive"))
    )
    (net (code "55") (name "Net-(U1-VCCIO)") (class "Default")
      (node (ref "C3") (pin "1") (pinfunction "1_1") (pintype "passive"))
      (node (ref "U1") (pin "37") (pinfunction "VCCIO_37") (pintype "passive"))
    )
    (net (code "56") (name "Net-(U1-VSET)") (class "Default")
      (node (ref "R9") (pin "1") (pinfunction "1_1") (pintype "passive"))
      (node (ref "U1") (pin "41") (pinfunction "VSET_41") (pintype "passive"))
    )
    (net (code "57") (name "Net-(U4-CS)") (class "Default")
      (node (ref "R22") (pin "2") (pinfunction "2_2") (pintype "passive"))
      (node (ref "U4") (pin "3") (pinfunction "CS_3") (pintype "passive"))
    )
    (net (code "58") (name "Net-(U4-VC)") (class "Default")
      (node (ref "C21") (pin "2") (pinfunction "2_2") (pintype "passive"))
      (node (ref "R23") (pin "1") (pinfunction "1_1") (pintype "passive"))
      (node (ref "U4") (pin "4") (pinfunction "VC_4") (pintype "passive"))
    )
    (net (code "59") (name "Net-(U4-VDD)") (class "Default")
      (node (ref "C20") (pin "2") (pinfunction "2_2") (pintype "passive"))
      (node (ref "R21") (pin "1") (pinfunction "1_1") (pintype "passive"))
      (node (ref "U4") (pin "5") (pinfunction "VDD_5") (pintype "passive"))
    )
    (net (code "60") (name "Net-(U5-BIAS)") (class "Default")
      (node (ref "C22") (pin "1") (pinfunction "1_1") (pintype "passive"))
      (node (ref "U5") (pin "3") (pinfunction "BIAS_3") (pintype "passive"))
    )
    (net (code "61") (name "Net-(U5-ISET)") (class "Default")
      (node (ref "C19") (pin "2") (pinfunction "2_2") (pintype "passive"))
      (node (ref "R24") (pin "2") (pinfunction "2_2") (pintype "passive"))
      (node (ref "U5") (pin "1") (pinfunction "ISET_1") (pintype "passive"))
    )
    (net (code "62") (name "Net-(U5-SW)") (class "Default")
      (node (ref "C22") (pin "2") (pinfunction "2_2") (pintype "passive"))
      (node (ref "L2") (pin "1") (pinfunction "1_1") (pintype "passive"))
      (node (ref "U5") (pin "4") (pinfunction "SW_4") (pintype "passive"))
    )
    (net (code "63") (name "unconnected-(U1-DMA1-Pad56)") (class "Default")
      (node (ref "U1") (pin "56") (pinfunction "DMA1_56") (pintype "passive+no_connect"))
    )
    (net (code "64") (name "unconnected-(U1-DMA2-Pad61)") (class "Default")
      (node (ref "U1") (pin "61") (pinfunction "DMA2_61") (pintype "passive+no_connect"))
    )
    (net (code "65") (name "unconnected-(U1-DPA1-Pad55)") (class "Default")
      (node (ref "U1") (pin "55") (pinfunction "DPA1_55") (pintype "passive+no_connect"))
    )
    (net (code "66") (name "unconnected-(U1-DPA2-Pad60)") (class "Default")
      (node (ref "U1") (pin "60") (pinfunction "DPA2_60") (pintype "passive+no_connect"))
    )
    (net (code "67") (name "unconnected-(U1-GPIO9-Pad6)") (class "Default")
      (node (ref "U1") (pin "6") (pinfunction "GPIO9_6") (pintype "passive+no_connect"))
    )
    (net (code "68") (name "unconnected-(U1-GPIO10-Pad7)") (class "Default")
      (node (ref "U1") (pin "7") (pinfunction "GPIO10_7") (pintype "passive+no_connect"))
    )
    (net (code "69") (name "unconnected-(U1-IGND-Pad42)") (class "Default")
      (node (ref "U1") (pin "42") (pinfunction "IGND_42") (pintype "passive+no_connect"))
    )
    (net (code "70") (name "unconnected-(U1-ISENSE-Pad43)") (class "Default")
      (node (ref "U1") (pin "43") (pinfunction "ISENSE_43") (pintype "passive+no_connect"))
    )
    (net (code "71") (name "unconnected-(U1-LED6-Pad38)") (class "Default")
      (node (ref "U1") (pin "38") (pinfunction "LED6_38") (pintype "passive+no_connect"))
    )
    (net (code "72") (name "unconnected-(U1-LT-Pad1)") (class "Default")
      (node (ref "U1") (pin "1") (pinfunction "LT_1") (pintype "passive+no_connect"))
    )
    (net (code "73") (name "unconnected-(U1-LX-Pad33)") (class "Default")
      (node (ref "U1") (pin "33") (pinfunction "LX_33") (pintype "passive+no_connect"))
    )
    (net (code "74") (name "unconnected-(U1-VOUT1-Pad57)") (class "Default")
      (node (ref "U1") (pin "57") (pinfunction "VOUT1_57") (pintype "passive+no_connect"))
    )
    (net (code "75") (name "unconnected-(U1-VOUT1G-Pad58)") (class "Default")
      (node (ref "U1") (pin "58") (pinfunction "VOUT1G_58") (pintype "passive+no_connect"))
    )
    (net (code "76") (name "unconnected-(U1-VOUT1_I-Pad59)") (class "Default")
      (node (ref "U1") (pin "59") (pinfunction "VOUT1_I_59") (pintype "passive+no_connect"))
    )
    (net (code "77") (name "unconnected-(U1-VOUT2-Pad62)") (class "Default")
      (node (ref "U1") (pin "62") (pinfunction "VOUT2_62") (pintype "passive+no_connect"))
    )
    (net (code "78") (name "unconnected-(U1-VOUT2G-Pad63)") (class "Default")
      (node (ref "U1") (pin "63") (pinfunction "VOUT2G_63") (pintype "passive+no_connect"))
    )
    (net (code "79") (name "unconnected-(U1-VOUT2_I-Pad64)") (class "Default")
      (node (ref "U1") (pin "64") (pinfunction "VOUT2_I_64") (pintype "passive+no_connect"))
    )
    (net (code "80") (name "unconnected-(USB1-SBU1-Pad9)") (class "Default")
      (node (ref "USB1") (pin "9") (pinfunction "SBU1_9") (pintype "passive+no_connect"))
    )
    (net (code "81") (name "unconnected-(USB1-SBU2-Pad3)") (class "Default")
      (node (ref "USB1") (pin "3") (pinfunction "SBU2_3") (pintype "passive+no_connect"))
    )
  )
)
